# i-ching_2020-06-26_04-06-56.net
KiCad netlist of a schematic drawn in EasyEDA
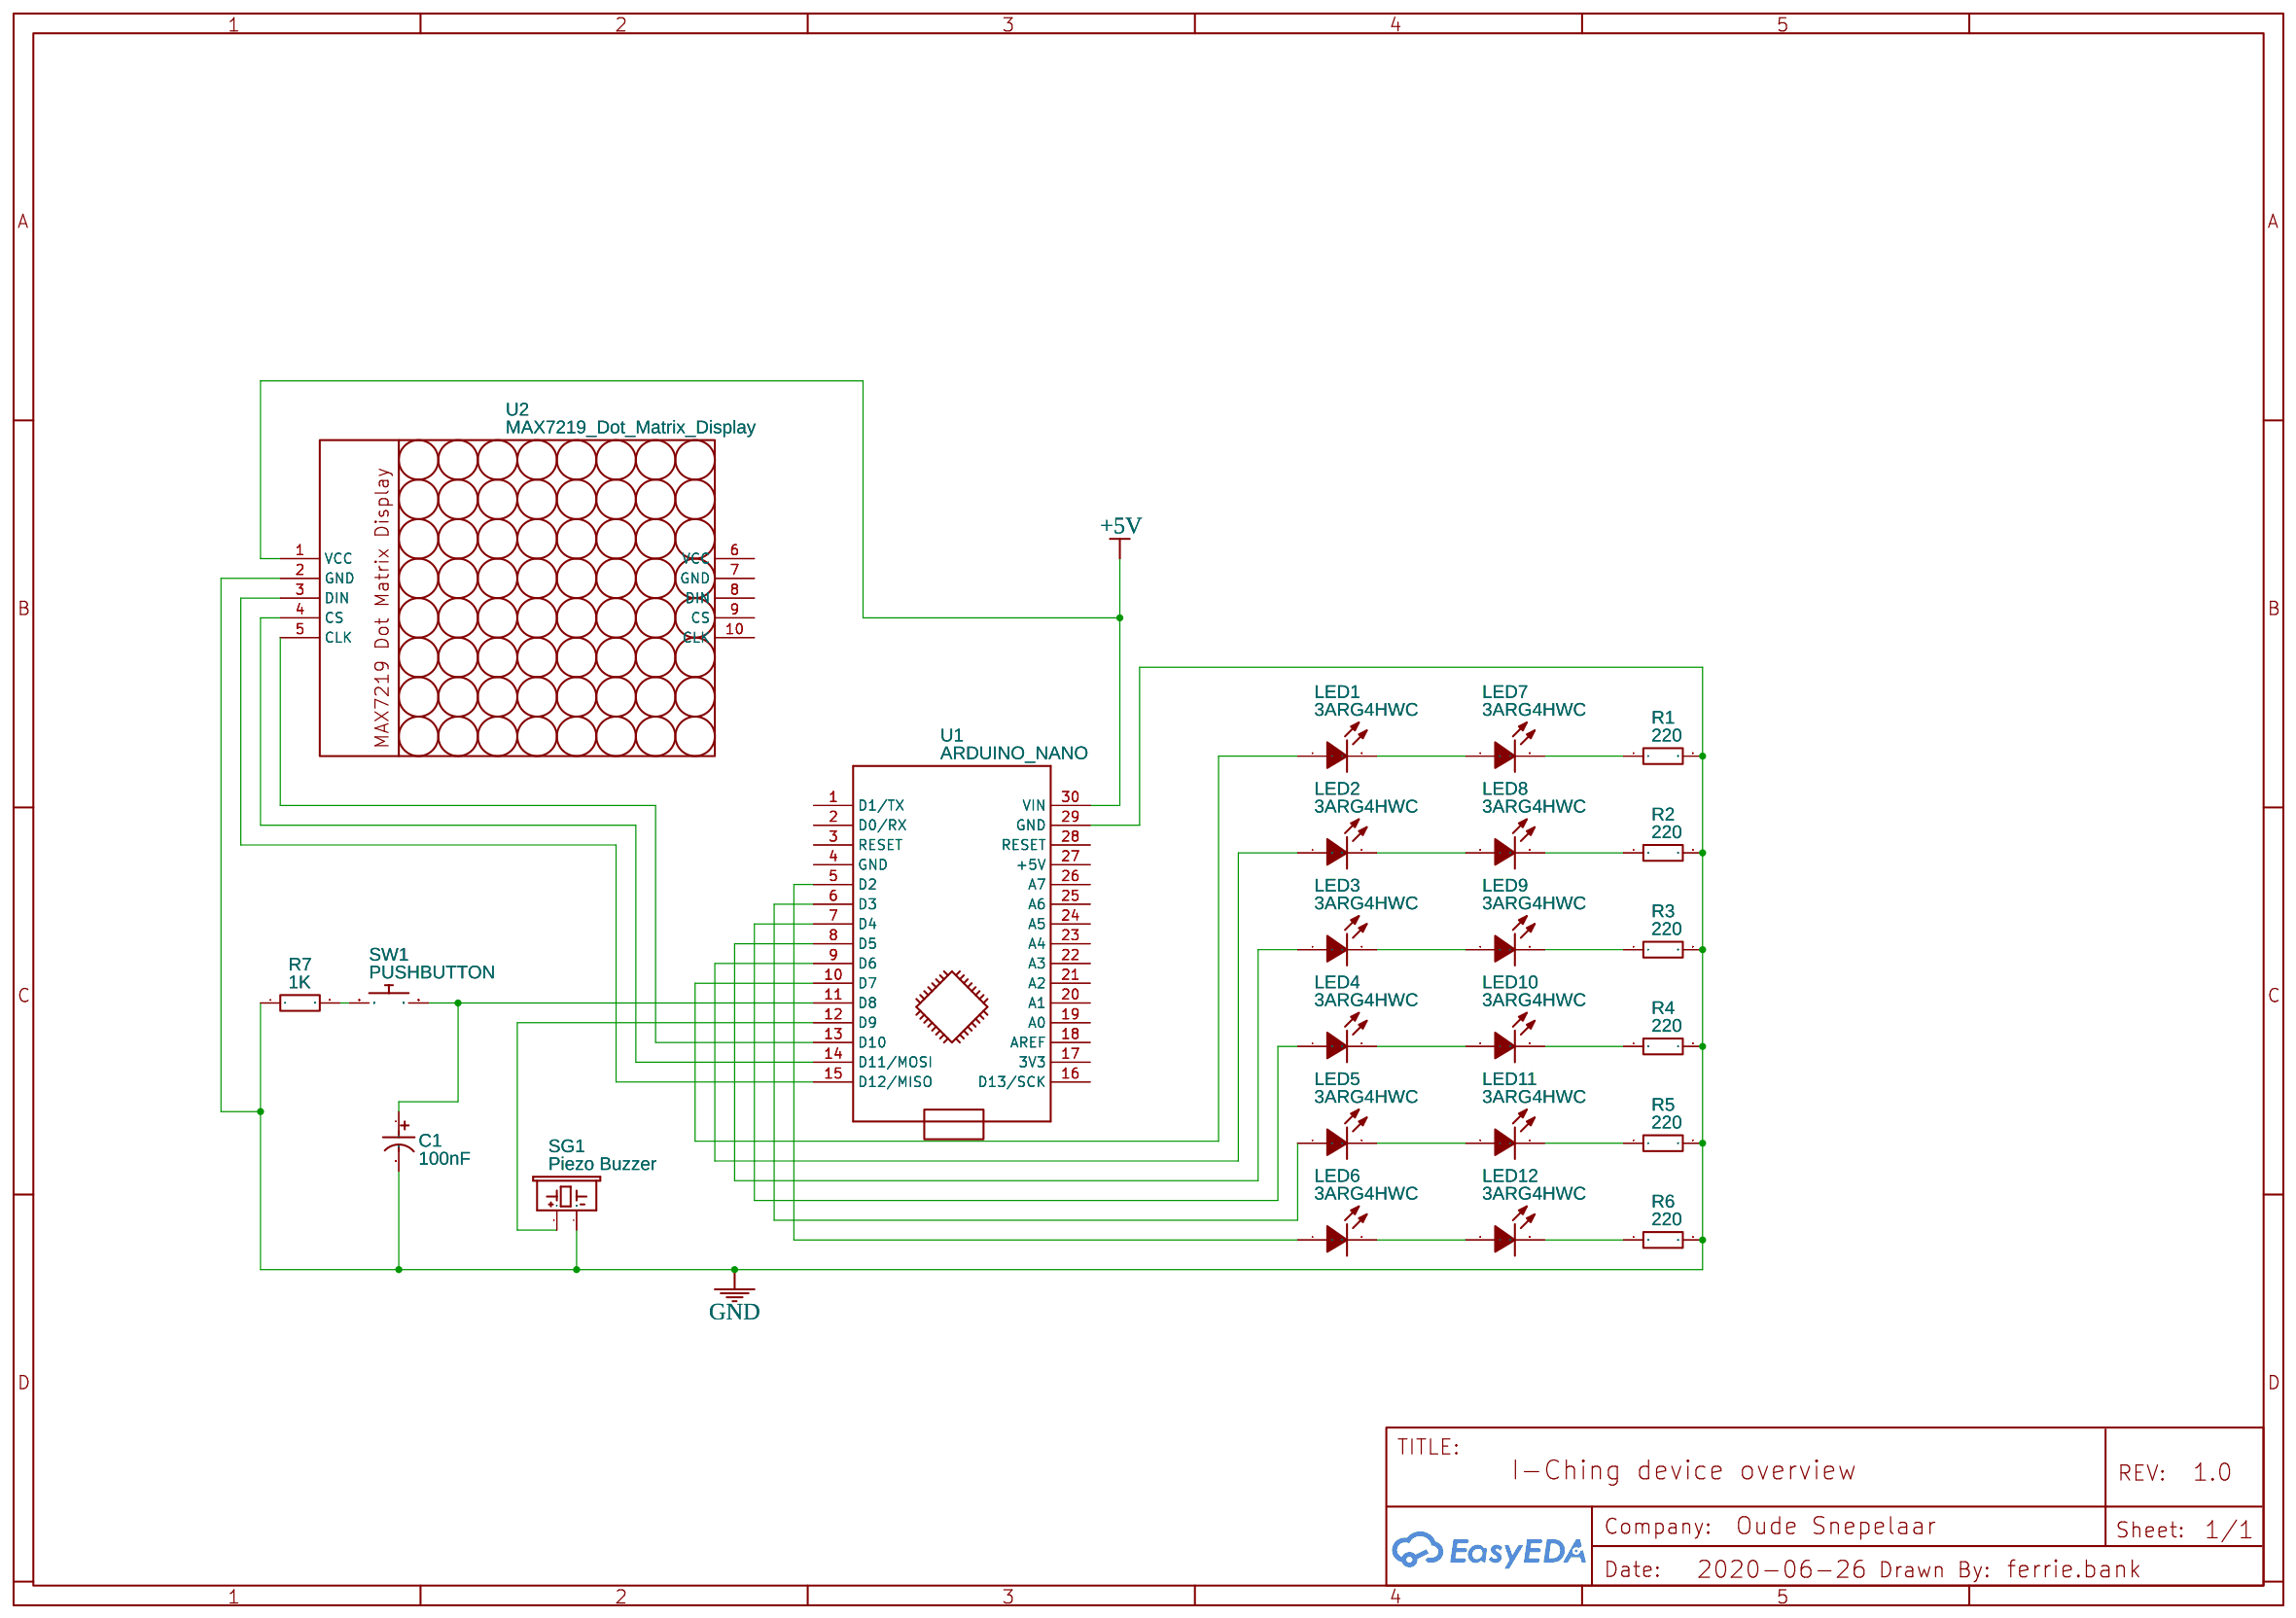
[diagram p0: I-Ching device overview]
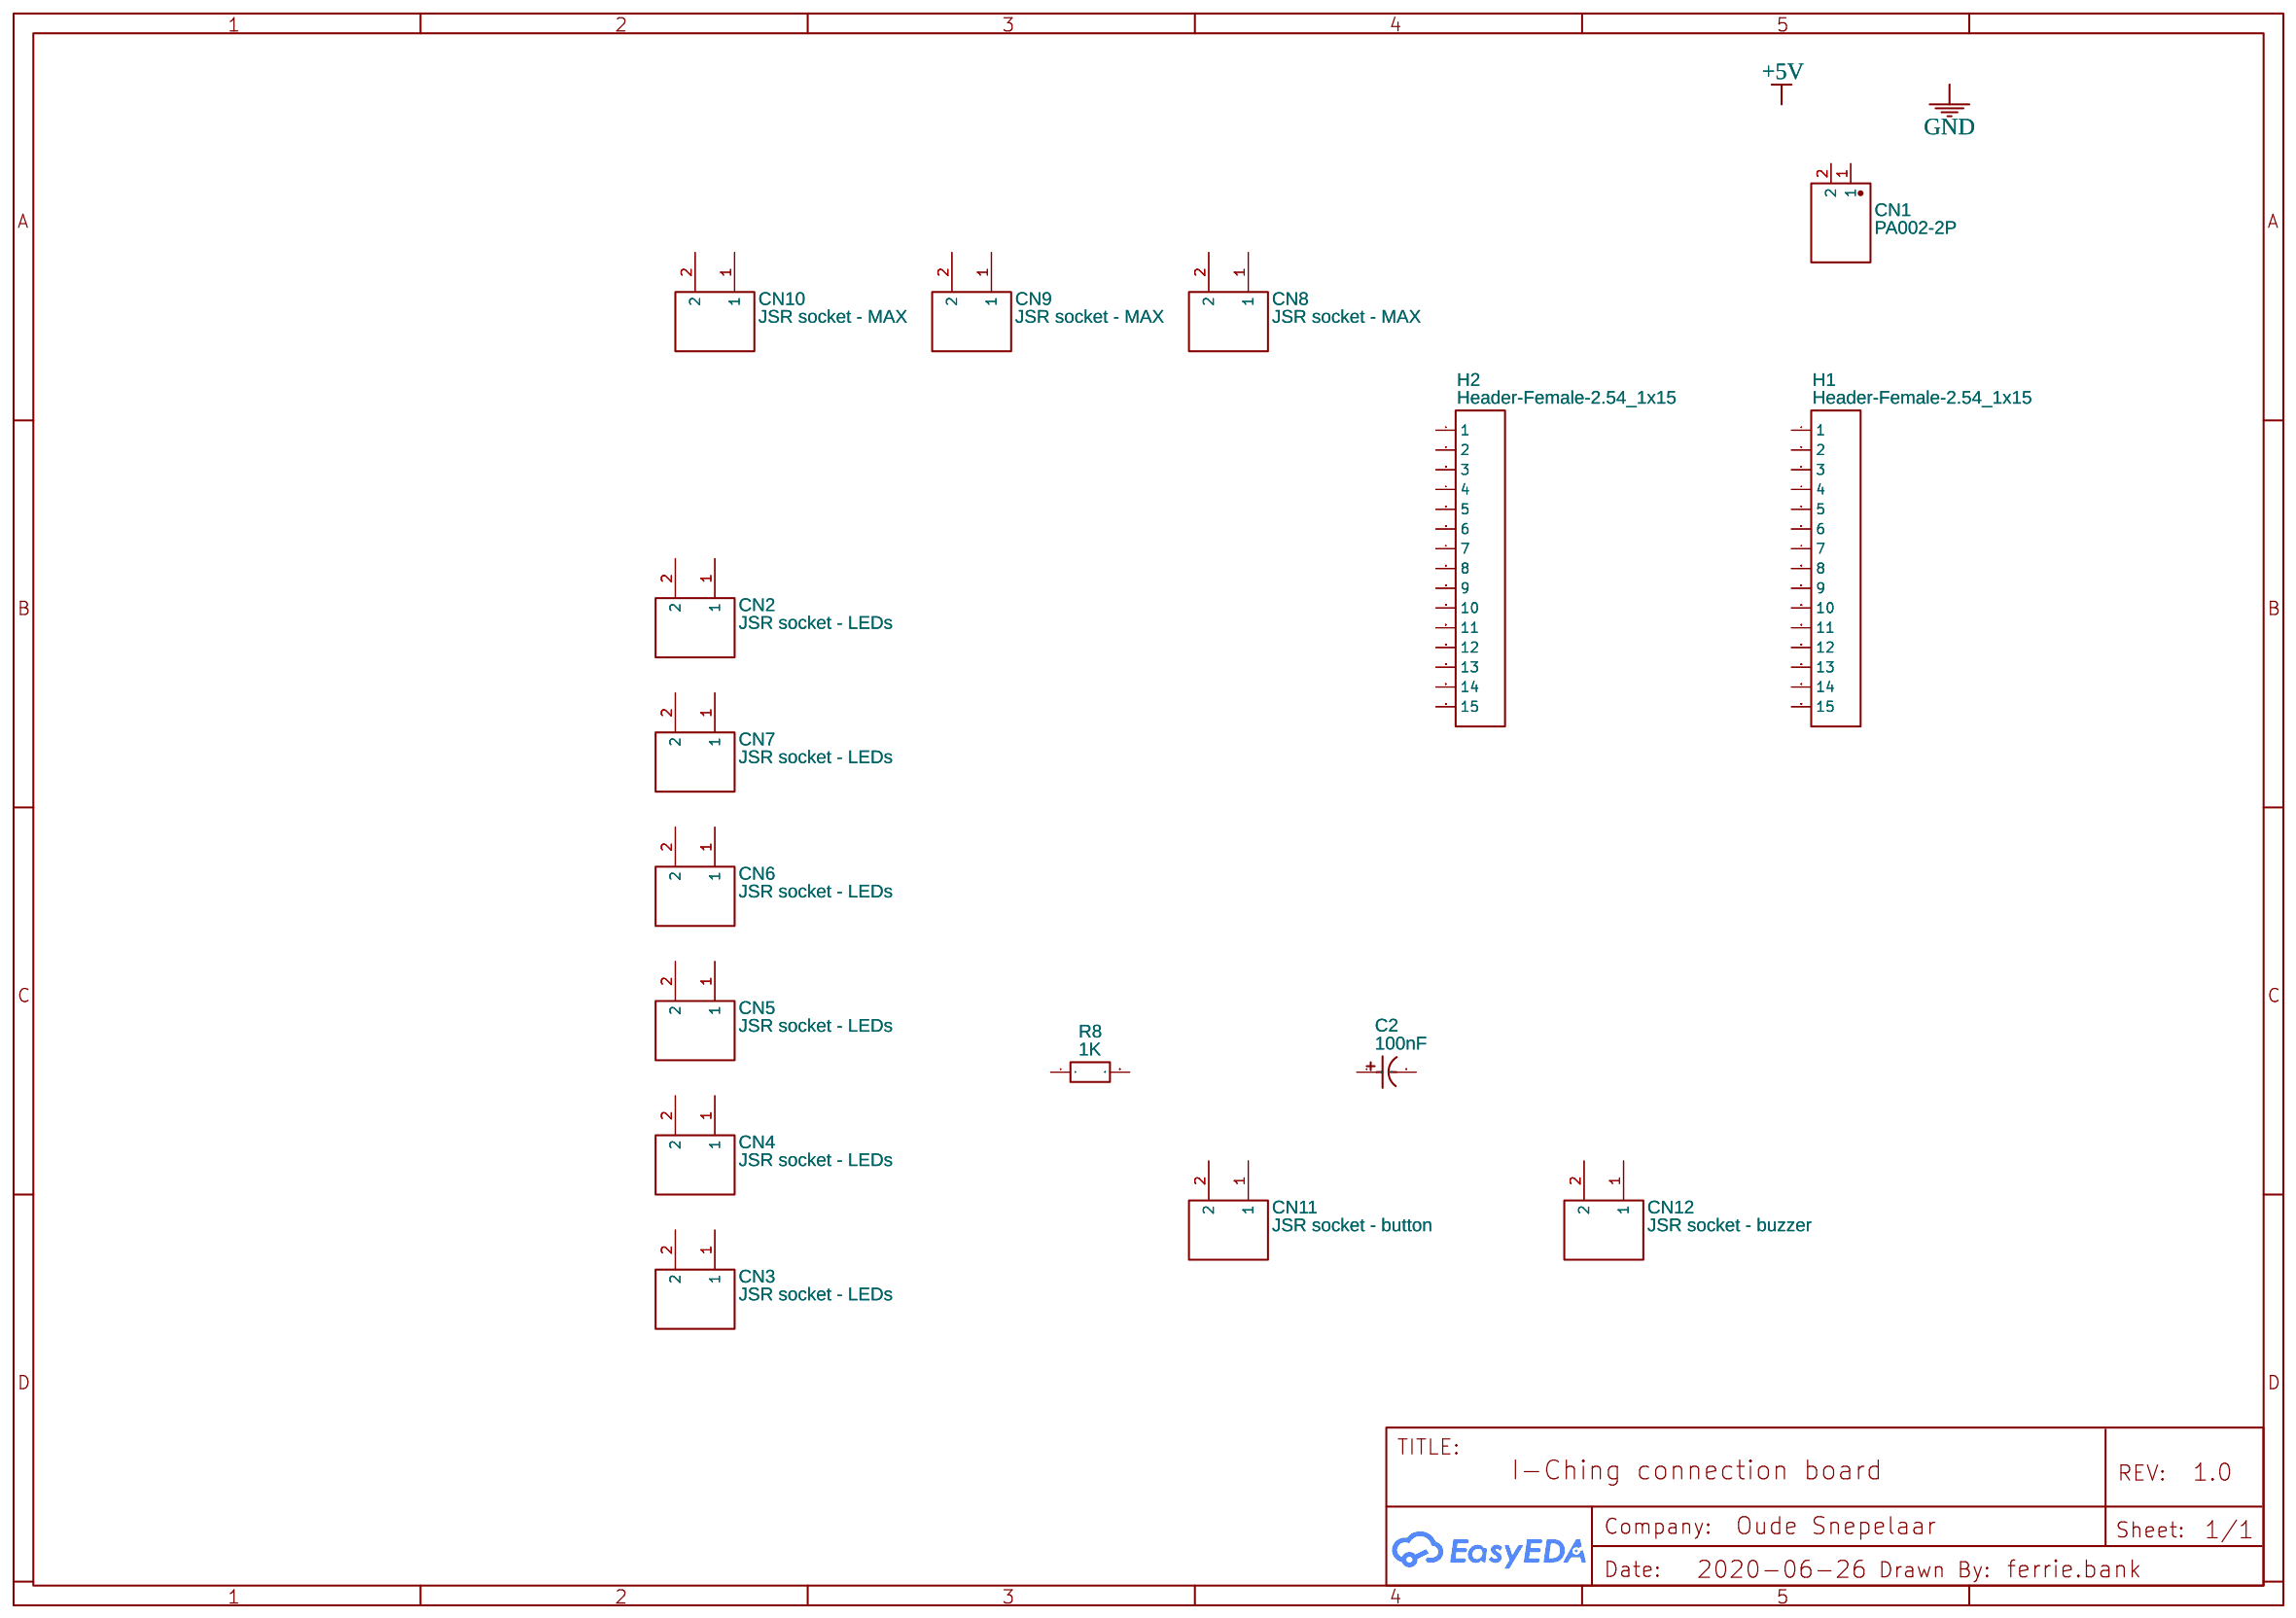
[diagram p1: I-Ching connection board]

(export (version "E")
  (design (tool "Eeschema 10.0.6"))
  (components
    (comp (ref "C1")
      (value "100nF")
      (fields (field (name "BOM_Manufacturer Part") "0.1UF 50V") (field (name "BOM_Supplier Part") "C28061"))
      (libsource (lib "") (part "0.1UF 50V"))
    )
    (comp (ref "LED1")
      (value "3ARG4HWC")
      (fields (field (name "BOM_Supplier Part") "C55640"))
      (libsource (lib "") (part "3ARG4HWC"))
    )
    (comp (ref "LED2")
      (value "3ARG4HWC")
      (fields (field (name "BOM_Supplier Part") "C55640"))
      (libsource (lib "") (part "3ARG4HWC"))
    )
    (comp (ref "LED3")
      (value "3ARG4HWC")
      (fields (field (name "BOM_Supplier Part") "C55640"))
      (libsource (lib "") (part "3ARG4HWC"))
    )
    (comp (ref "LED4")
      (value "3ARG4HWC")
      (fields (field (name "BOM_Supplier Part") "C55640"))
      (libsource (lib "") (part "3ARG4HWC"))
    )
    (comp (ref "LED5")
      (value "3ARG4HWC")
      (fields (field (name "BOM_Supplier Part") "C55640"))
      (libsource (lib "") (part "3ARG4HWC"))
    )
    (comp (ref "LED6")
      (value "3ARG4HWC")
      (fields (field (name "BOM_Supplier Part") "C55640"))
      (libsource (lib "") (part "3ARG4HWC"))
    )
    (comp (ref "LED7")
      (value "3ARG4HWC")
      (fields (field (name "BOM_Supplier Part") "C55640"))
      (libsource (lib "") (part "3ARG4HWC"))
    )
    (comp (ref "LED8")
      (value "3ARG4HWC")
      (fields (field (name "BOM_Supplier Part") "C55640"))
      (libsource (lib "") (part "3ARG4HWC"))
    )
    (comp (ref "LED9")
      (value "3ARG4HWC")
      (fields (field (name "BOM_Supplier Part") "C55640"))
      (libsource (lib "") (part "3ARG4HWC"))
    )
    (comp (ref "LED10")
      (value "3ARG4HWC")
      (fields (field (name "BOM_Supplier Part") "C55640"))
      (libsource (lib "") (part "3ARG4HWC"))
    )
    (comp (ref "LED11")
      (value "3ARG4HWC")
      (fields (field (name "BOM_Supplier Part") "C55640"))
      (libsource (lib "") (part "3ARG4HWC"))
    )
    (comp (ref "LED12")
      (value "3ARG4HWC")
      (fields (field (name "BOM_Supplier Part") "C55640"))
      (libsource (lib "") (part "3ARG4HWC"))
    )
    (comp (ref "R1")
      (value "220")
      (fields
        (field (name "BOM_Manufacturer Part") "MFR2WSJT-73-220R")
        (field (name "BOM_Supplier Part") "C176568")
      )
      (libsource (lib "") (part "MFR2WSJT-73-220R"))
    )
    (comp (ref "R2")
      (value "220")
      (fields
        (field (name "BOM_Manufacturer Part") "MFR2WSJT-73-220R")
        (field (name "BOM_Supplier Part") "C176568")
      )
      (libsource (lib "") (part "MFR2WSJT-73-220R"))
    )
    (comp (ref "R3")
      (value "220")
      (fields
        (field (name "BOM_Manufacturer Part") "MFR2WSJT-73-220R")
        (field (name "BOM_Supplier Part") "C176568")
      )
      (libsource (lib "") (part "MFR2WSJT-73-220R"))
    )
    (comp (ref "R4")
      (value "220")
      (fields
        (field (name "BOM_Manufacturer Part") "MFR2WSJT-73-220R")
        (field (name "BOM_Supplier Part") "C176568")
      )
      (libsource (lib "") (part "MFR2WSJT-73-220R"))
    )
    (comp (ref "R5")
      (value "220")
      (fields
        (field (name "BOM_Manufacturer Part") "MFR2WSJT-73-220R")
        (field (name "BOM_Supplier Part") "C176568")
      )
      (libsource (lib "") (part "MFR2WSJT-73-220R"))
    )
    (comp (ref "R6")
      (value "220")
      (fields
        (field (name "BOM_Manufacturer Part") "MFR2WSJT-73-220R")
        (field (name "BOM_Supplier Part") "C176568")
      )
      (libsource (lib "") (part "MFR2WSJT-73-220R"))
    )
    (comp (ref "R7")
      (value "1K")
      (fields
        (field (name "BOM_Manufacturer Part") "MFR02SF1001A10")
        (field (name "BOM_Supplier Part") "C58742")
      )
      (libsource (lib "") (part "MFR02SF1001A10"))
    )
    (comp (ref "SG1") (value "Piezo Buzzer") (libsource (lib "") (part "Piezo Buzzer")))
    (comp (ref "SW1") (value "PUSHBUTTON") (libsource (lib "") (part "SWITCH_PUSHBUTTONCK_KSS")))
    (comp (ref "U1") (value "ARDUINO_NANO") (libsource (lib "") (part "ARDUINO_NANO")))
    (comp (ref "U2")
      (value "MAX7219_Dot_Matrix_Display")
      (libsource (lib "") (part "MAX7219_Dot_Matrix_Display"))
    )
    (comp (ref "C2")
      (value "100nF")
      (fields (field (name "BOM_Manufacturer Part") "0.1UF 50V") (field (name "BOM_Supplier Part") "C28061"))
      (libsource (lib "") (part "0.1UF 50V"))
    )
    (comp (ref "CN1")
      (value "PA002-2P")
      (fields (field (name "BOM_Supplier Part") "C163148"))
      (libsource (lib "") (part "PA002-2P"))
    )
    (comp (ref "CN2")
      (value "JSR socket - LEDs")
      (fields
        (field (name "BOM_Manufacturer Part") "socket.blue5566-2Aneedle")
        (field (name "BOM_Supplier Part") "C62133")
      )
      (libsource (lib "") (part "socket.blue5566-2Aneedle"))
    )
    (comp (ref "CN3")
      (value "JSR socket - LEDs")
      (fields
        (field (name "BOM_Manufacturer Part") "socket.blue5566-2Aneedle")
        (field (name "BOM_Supplier Part") "C62133")
      )
      (libsource (lib "") (part "socket.blue5566-2Aneedle"))
    )
    (comp (ref "CN4")
      (value "JSR socket - LEDs")
      (fields
        (field (name "BOM_Manufacturer Part") "socket.blue5566-2Aneedle")
        (field (name "BOM_Supplier Part") "C62133")
      )
      (libsource (lib "") (part "socket.blue5566-2Aneedle"))
    )
    (comp (ref "CN5")
      (value "JSR socket - LEDs")
      (fields
        (field (name "BOM_Manufacturer Part") "socket.blue5566-2Aneedle")
        (field (name "BOM_Supplier Part") "C62133")
      )
      (libsource (lib "") (part "socket.blue5566-2Aneedle"))
    )
    (comp (ref "CN6")
      (value "JSR socket - LEDs")
      (fields
        (field (name "BOM_Manufacturer Part") "socket.blue5566-2Aneedle")
        (field (name "BOM_Supplier Part") "C62133")
      )
      (libsource (lib "") (part "socket.blue5566-2Aneedle"))
    )
    (comp (ref "CN7")
      (value "JSR socket - LEDs")
      (fields
        (field (name "BOM_Manufacturer Part") "socket.blue5566-2Aneedle")
        (field (name "BOM_Supplier Part") "C62133")
      )
      (libsource (lib "") (part "socket.blue5566-2Aneedle"))
    )
    (comp (ref "CN8")
      (value "JSR socket - MAX")
      (fields
        (field (name "BOM_Manufacturer Part") "socket.blue5566-2Aneedle")
        (field (name "BOM_Supplier Part") "C62133")
      )
      (libsource (lib "") (part "socket.blue5566-2Aneedle"))
    )
    (comp (ref "CN9")
      (value "JSR socket - MAX")
      (fields
        (field (name "BOM_Manufacturer Part") "socket.blue5566-2Aneedle")
        (field (name "BOM_Supplier Part") "C62133")
      )
      (libsource (lib "") (part "socket.blue5566-2Aneedle"))
    )
    (comp (ref "CN10")
      (value "JSR socket - MAX")
      (fields
        (field (name "BOM_Manufacturer Part") "socket.blue5566-2Aneedle")
        (field (name "BOM_Supplier Part") "C62133")
      )
      (libsource (lib "") (part "socket.blue5566-2Aneedle"))
    )
    (comp (ref "CN11")
      (value "JSR socket - button")
      (fields
        (field (name "BOM_Manufacturer Part") "socket.blue5566-2Aneedle")
        (field (name "BOM_Supplier Part") "C62133")
      )
      (libsource (lib "") (part "socket.blue5566-2Aneedle"))
    )
    (comp (ref "CN12")
      (value "JSR socket - buzzer")
      (fields
        (field (name "BOM_Manufacturer Part") "socket.blue5566-2Aneedle")
        (field (name "BOM_Supplier Part") "C62133")
      )
      (libsource (lib "") (part "socket.blue5566-2Aneedle"))
    )
    (comp (ref "H1")
      (value "Header-Female-2.54_1x15")
      (fields
        (field (name "BOM_Manufacturer Part") "220S-1*15P H=8.5MM Ytype Gold-plated")
        (field (name "BOM_Supplier Part") "C124408")
      )
      (libsource (lib "") (part "Header-Female-2.54_1x15"))
    )
    (comp (ref "H2")
      (value "Header-Female-2.54_1x15")
      (fields
        (field (name "BOM_Manufacturer Part") "220S-1*15P H=8.5MM Ytype Gold-plated")
        (field (name "BOM_Supplier Part") "C124408")
      )
      (libsource (lib "") (part "Header-Female-2.54_1x15"))
    )
    (comp (ref "R8")
      (value "1K")
      (fields
        (field (name "BOM_Manufacturer Part") "RN 2WS 1K F T/B A1")
        (field (name "BOM_Supplier Part") "C433624")
      )
      (libsource (lib "") (part "RN 2WS 1K F T/B A1_C433624"))
    )
  )
  (nets
    (net (code "1") (name "+5V") (class "Default")
      (node (ref "U1") (pin "30") (pinfunction "VIN_30") (pintype "unspecified"))
      (node (ref "U2") (pin "1") (pinfunction "VCC_1") (pintype "unspecified"))
    )
    (net (code "2") (name "GND") (class "Default")
      (node (ref "C1") (pin "2") (pinfunction "2_2") (pintype "input"))
      (node (ref "R1") (pin "2") (pinfunction "2_2") (pintype "input"))
      (node (ref "R2") (pin "2") (pinfunction "2_2") (pintype "input"))
      (node (ref "R3") (pin "2") (pinfunction "2_2") (pintype "input"))
      (node (ref "R4") (pin "2") (pinfunction "2_2") (pintype "input"))
      (node (ref "R5") (pin "2") (pinfunction "2_2") (pintype "input"))
      (node (ref "R6") (pin "2") (pinfunction "2_2") (pintype "input"))
      (node (ref "R7") (pin "1") (pinfunction "1_1") (pintype "input"))
      (node (ref "SG1") (pin "-") (pinfunction "2_-") (pintype "unspecified"))
      (node (ref "U1") (pin "29") (pinfunction "GND_29") (pintype "unspecified"))
      (node (ref "U2") (pin "2") (pinfunction "GND_2") (pintype "unspecified"))
    )
    (net (code "3") (name "Net-(LED1-A)") (class "Default")
      (node (ref "LED1") (pin "1") (pinfunction "A_1") (pintype "unspecified"))
      (node (ref "U1") (pin "10") (pinfunction "D7_10") (pintype "unspecified"))
    )
    (net (code "4") (name "Net-(LED1-K)") (class "Default")
      (node (ref "LED1") (pin "2") (pinfunction "K_2") (pintype "unspecified"))
      (node (ref "LED7") (pin "1") (pinfunction "A_1") (pintype "unspecified"))
    )
    (net (code "5") (name "Net-(LED2-A)") (class "Default")
      (node (ref "LED2") (pin "1") (pinfunction "A_1") (pintype "unspecified"))
      (node (ref "U1") (pin "9") (pinfunction "D6_9") (pintype "unspecified"))
    )
    (net (code "6") (name "Net-(LED2-K)") (class "Default")
      (node (ref "LED2") (pin "2") (pinfunction "K_2") (pintype "unspecified"))
      (node (ref "LED8") (pin "1") (pinfunction "A_1") (pintype "unspecified"))
    )
    (net (code "7") (name "Net-(LED3-A)") (class "Default")
      (node (ref "LED3") (pin "1") (pinfunction "A_1") (pintype "unspecified"))
      (node (ref "U1") (pin "8") (pinfunction "D5_8") (pintype "unspecified"))
    )
    (net (code "8") (name "Net-(LED3-K)") (class "Default")
      (node (ref "LED3") (pin "2") (pinfunction "K_2") (pintype "unspecified"))
      (node (ref "LED9") (pin "1") (pinfunction "A_1") (pintype "unspecified"))
    )
    (net (code "9") (name "Net-(LED4-A)") (class "Default")
      (node (ref "LED4") (pin "1") (pinfunction "A_1") (pintype "unspecified"))
      (node (ref "U1") (pin "7") (pinfunction "D4_7") (pintype "unspecified"))
    )
    (net (code "10") (name "Net-(LED5-A)") (class "Default")
      (node (ref "LED5") (pin "1") (pinfunction "A_1") (pintype "unspecified"))
      (node (ref "U1") (pin "6") (pinfunction "D3_6") (pintype "unspecified"))
    )
    (net (code "11") (name "Net-(LED6-A)") (class "Default")
      (node (ref "LED6") (pin "1") (pinfunction "A_1") (pintype "unspecified"))
      (node (ref "U1") (pin "5") (pinfunction "D2_5") (pintype "unspecified"))
    )
    (net (code "12") (name "Net-(LED7-K)") (class "Default")
      (node (ref "LED7") (pin "2") (pinfunction "K_2") (pintype "unspecified"))
      (node (ref "R1") (pin "1") (pinfunction "1_1") (pintype "input"))
    )
    (net (code "13") (name "Net-(LED8-K)") (class "Default")
      (node (ref "LED8") (pin "2") (pinfunction "K_2") (pintype "unspecified"))
      (node (ref "R2") (pin "1") (pinfunction "1_1") (pintype "input"))
    )
    (net (code "14") (name "Net-(LED9-K)") (class "Default")
      (node (ref "LED9") (pin "2") (pinfunction "K_2") (pintype "unspecified"))
      (node (ref "R3") (pin "1") (pinfunction "1_1") (pintype "input"))
    )
    (net (code "15") (name "Net-(LED10-A)") (class "Default")
      (node (ref "LED10") (pin "1") (pinfunction "A_1") (pintype "unspecified"))
      (node (ref "LED4") (pin "2") (pinfunction "K_2") (pintype "unspecified"))
    )
    (net (code "16") (name "Net-(LED10-K)") (class "Default")
      (node (ref "LED10") (pin "2") (pinfunction "K_2") (pintype "unspecified"))
      (node (ref "R4") (pin "1") (pinfunction "1_1") (pintype "input"))
    )
    (net (code "17") (name "Net-(LED11-A)") (class "Default")
      (node (ref "LED11") (pin "1") (pinfunction "A_1") (pintype "unspecified"))
      (node (ref "LED5") (pin "2") (pinfunction "K_2") (pintype "unspecified"))
    )
    (net (code "18") (name "Net-(LED11-K)") (class "Default")
      (node (ref "LED11") (pin "2") (pinfunction "K_2") (pintype "unspecified"))
      (node (ref "R5") (pin "1") (pinfunction "1_1") (pintype "input"))
    )
    (net (code "19") (name "Net-(LED12-A)") (class "Default")
      (node (ref "LED12") (pin "1") (pinfunction "A_1") (pintype "unspecified"))
      (node (ref "LED6") (pin "2") (pinfunction "K_2") (pintype "unspecified"))
    )
    (net (code "20") (name "Net-(LED12-K)") (class "Default")
      (node (ref "LED12") (pin "2") (pinfunction "K_2") (pintype "unspecified"))
      (node (ref "R6") (pin "1") (pinfunction "1_1") (pintype "input"))
    )
    (net (code "21") (name "Net-(R7-Pad2)") (class "Default")
      (node (ref "R7") (pin "2") (pinfunction "2_2") (pintype "input"))
      (node (ref "SW1") (pin "P$1") (pinfunction "P$1_P$1") (pintype "unspecified"))
    )
    (net (code "22") (name "Net-(SG1-1)") (class "Default")
      (node (ref "SG1") (pin "+") (pinfunction "1_+") (pintype "unspecified"))
      (node (ref "U1") (pin "12") (pinfunction "D9_12") (pintype "unspecified"))
    )
    (net (code "23") (name "Net-(U1-D8)") (class "Default")
      (node (ref "C1") (pin "1") (pinfunction "1_1") (pintype "input"))
      (node (ref "SW1") (pin "P$2") (pinfunction "P$2_P$2") (pintype "unspecified"))
      (node (ref "U1") (pin "11") (pinfunction "D8_11") (pintype "unspecified"))
    )
    (net (code "24") (name "Net-(U1-D10)") (class "Default")
      (node (ref "U1") (pin "13") (pinfunction "D10_13") (pintype "unspecified"))
      (node (ref "U2") (pin "5") (pinfunction "CLK_5") (pintype "unspecified"))
    )
    (net (code "25") (name "Net-(U1-D11{slash}MOSI)") (class "Default")
      (node (ref "U1") (pin "14") (pinfunction "D11/MOSI_14") (pintype "unspecified"))
      (node (ref "U2") (pin "4") (pinfunction "CS_4") (pintype "unspecified"))
    )
    (net (code "26") (name "Net-(U1-D12{slash}MISO)") (class "Default")
      (node (ref "U1") (pin "15") (pinfunction "D12/MISO_15") (pintype "unspecified"))
      (node (ref "U2") (pin "3") (pinfunction "DIN_3") (pintype "unspecified"))
    )
    (net (code "27") (name "unconnected-(C2-Pad1)") (class "Default")
      (node (ref "C2") (pin "1") (pinfunction "1_1") (pintype "input"))
    )
    (net (code "28") (name "unconnected-(C2-Pad2)") (class "Default")
      (node (ref "C2") (pin "2") (pinfunction "2_2") (pintype "input"))
    )
    (net (code "29") (name "unconnected-(CN1-Pad1)") (class "Default")
      (node (ref "CN1") (pin "1") (pinfunction "1_1") (pintype "unspecified"))
    )
    (net (code "30") (name "unconnected-(CN1-Pad2)") (class "Default")
      (node (ref "CN1") (pin "2") (pinfunction "2_2") (pintype "unspecified"))
    )
    (net (code "31") (name "unconnected-(CN2-Pad1)") (class "Default")
      (node (ref "CN2") (pin "1") (pinfunction "1_1") (pintype "unspecified"))
    )
    (net (code "32") (name "unconnected-(CN2-Pad2)") (class "Default")
      (node (ref "CN2") (pin "2") (pinfunction "2_2") (pintype "unspecified"))
    )
    (net (code "33") (name "unconnected-(CN3-Pad1)") (class "Default")
      (node (ref "CN3") (pin "1") (pinfunction "1_1") (pintype "unspecified"))
    )
    (net (code "34") (name "unconnected-(CN3-Pad2)") (class "Default")
      (node (ref "CN3") (pin "2") (pinfunction "2_2") (pintype "unspecified"))
    )
    (net (code "35") (name "unconnected-(CN4-Pad1)") (class "Default")
      (node (ref "CN4") (pin "1") (pinfunction "1_1") (pintype "unspecified"))
    )
    (net (code "36") (name "unconnected-(CN4-Pad2)") (class "Default")
      (node (ref "CN4") (pin "2") (pinfunction "2_2") (pintype "unspecified"))
    )
    (net (code "37") (name "unconnected-(CN5-Pad1)") (class "Default")
      (node (ref "CN5") (pin "1") (pinfunction "1_1") (pintype "unspecified"))
    )
    (net (code "38") (name "unconnected-(CN5-Pad2)") (class "Default")
      (node (ref "CN5") (pin "2") (pinfunction "2_2") (pintype "unspecified"))
    )
    (net (code "39") (name "unconnected-(CN6-Pad1)") (class "Default")
      (node (ref "CN6") (pin "1") (pinfunction "1_1") (pintype "unspecified"))
    )
    (net (code "40") (name "unconnected-(CN6-Pad2)") (class "Default")
      (node (ref "CN6") (pin "2") (pinfunction "2_2") (pintype "unspecified"))
    )
    (net (code "41") (name "unconnected-(CN7-Pad1)") (class "Default")
      (node (ref "CN7") (pin "1") (pinfunction "1_1") (pintype "unspecified"))
    )
    (net (code "42") (name "unconnected-(CN7-Pad2)") (class "Default")
      (node (ref "CN7") (pin "2") (pinfunction "2_2") (pintype "unspecified"))
    )
    (net (code "43") (name "unconnected-(CN8-Pad1)") (class "Default")
      (node (ref "CN8") (pin "1") (pinfunction "1_1") (pintype "unspecified"))
    )
    (net (code "44") (name "unconnected-(CN8-Pad2)") (class "Default")
      (node (ref "CN8") (pin "2") (pinfunction "2_2") (pintype "unspecified"))
    )
    (net (code "45") (name "unconnected-(CN9-Pad1)") (class "Default")
      (node (ref "CN9") (pin "1") (pinfunction "1_1") (pintype "unspecified"))
    )
    (net (code "46") (name "unconnected-(CN9-Pad2)") (class "Default")
      (node (ref "CN9") (pin "2") (pinfunction "2_2") (pintype "unspecified"))
    )
    (net (code "47") (name "unconnected-(CN10-Pad1)") (class "Default")
      (node (ref "CN10") (pin "1") (pinfunction "1_1") (pintype "unspecified"))
    )
    (net (code "48") (name "unconnected-(CN10-Pad2)") (class "Default")
      (node (ref "CN10") (pin "2") (pinfunction "2_2") (pintype "unspecified"))
    )
    (net (code "49") (name "unconnected-(CN11-Pad1)") (class "Default")
      (node (ref "CN11") (pin "1") (pinfunction "1_1") (pintype "unspecified"))
    )
    (net (code "50") (name "unconnected-(CN11-Pad2)") (class "Default")
      (node (ref "CN11") (pin "2") (pinfunction "2_2") (pintype "unspecified"))
    )
    (net (code "51") (name "unconnected-(CN12-Pad1)") (class "Default")
      (node (ref "CN12") (pin "1") (pinfunction "1_1") (pintype "unspecified"))
    )
    (net (code "52") (name "unconnected-(CN12-Pad2)") (class "Default")
      (node (ref "CN12") (pin "2") (pinfunction "2_2") (pintype "unspecified"))
    )
    (net (code "53") (name "unconnected-(H1-Pad1)") (class "Default")
      (node (ref "H1") (pin "1") (pinfunction "1_1") (pintype "unspecified"))
    )
    (net (code "54") (name "unconnected-(H1-Pad2)") (class "Default")
      (node (ref "H1") (pin "2") (pinfunction "2_2") (pintype "unspecified"))
    )
    (net (code "55") (name "unconnected-(H1-Pad3)") (class "Default")
      (node (ref "H1") (pin "3") (pinfunction "3_3") (pintype "unspecified"))
    )
    (net (code "56") (name "unconnected-(H1-Pad4)") (class "Default")
      (node (ref "H1") (pin "4") (pinfunction "4_4") (pintype "unspecified"))
    )
    (net (code "57") (name "unconnected-(H1-Pad5)") (class "Default")
      (node (ref "H1") (pin "5") (pinfunction "5_5") (pintype "unspecified"))
    )
    (net (code "58") (name "unconnected-(H1-Pad6)") (class "Default")
      (node (ref "H1") (pin "6") (pinfunction "6_6") (pintype "unspecified"))
    )
    (net (code "59") (name "unconnected-(H1-Pad7)") (class "Default")
      (node (ref "H1") (pin "7") (pinfunction "7_7") (pintype "unspecified"))
    )
    (net (code "60") (name "unconnected-(H1-Pad8)") (class "Default")
      (node (ref "H1") (pin "8") (pinfunction "8_8") (pintype "unspecified"))
    )
    (net (code "61") (name "unconnected-(H1-Pad9)") (class "Default")
      (node (ref "H1") (pin "9") (pinfunction "9_9") (pintype "unspecified"))
    )
    (net (code "62") (name "unconnected-(H1-Pad10)") (class "Default")
      (node (ref "H1") (pin "10") (pinfunction "10_10") (pintype "unspecified"))
    )
    (net (code "63") (name "unconnected-(H1-Pad11)") (class "Default")
      (node (ref "H1") (pin "11") (pinfunction "11_11") (pintype "unspecified"))
    )
    (net (code "64") (name "unconnected-(H1-Pad12)") (class "Default")
      (node (ref "H1") (pin "12") (pinfunction "12_12") (pintype "unspecified"))
    )
    (net (code "65") (name "unconnected-(H1-Pad13)") (class "Default")
      (node (ref "H1") (pin "13") (pinfunction "13_13") (pintype "unspecified"))
    )
    (net (code "66") (name "unconnected-(H1-Pad14)") (class "Default")
      (node (ref "H1") (pin "14") (pinfunction "14_14") (pintype "unspecified"))
    )
    (net (code "67") (name "unconnected-(H1-Pad15)") (class "Default")
      (node (ref "H1") (pin "15") (pinfunction "15_15") (pintype "unspecified"))
    )
    (net (code "68") (name "unconnected-(H2-Pad1)") (class "Default")
      (node (ref "H2") (pin "1") (pinfunction "1_1") (pintype "unspecified"))
    )
    (net (code "69") (name "unconnected-(H2-Pad2)") (class "Default")
      (node (ref "H2") (pin "2") (pinfunction "2_2") (pintype "unspecified"))
    )
    (net (code "70") (name "unconnected-(H2-Pad3)") (class "Default")
      (node (ref "H2") (pin "3") (pinfunction "3_3") (pintype "unspecified"))
    )
    (net (code "71") (name "unconnected-(H2-Pad4)") (class "Default")
      (node (ref "H2") (pin "4") (pinfunction "4_4") (pintype "unspecified"))
    )
    (net (code "72") (name "unconnected-(H2-Pad5)") (class "Default")
      (node (ref "H2") (pin "5") (pinfunction "5_5") (pintype "unspecified"))
    )
    (net (code "73") (name "unconnected-(H2-Pad6)") (class "Default")
      (node (ref "H2") (pin "6") (pinfunction "6_6") (pintype "unspecified"))
    )
    (net (code "74") (name "unconnected-(H2-Pad7)") (class "Default")
      (node (ref "H2") (pin "7") (pinfunction "7_7") (pintype "unspecified"))
    )
    (net (code "75") (name "unconnected-(H2-Pad8)") (class "Default")
      (node (ref "H2") (pin "8") (pinfunction "8_8") (pintype "unspecified"))
    )
    (net (code "76") (name "unconnected-(H2-Pad9)") (class "Default")
      (node (ref "H2") (pin "9") (pinfunction "9_9") (pintype "unspecified"))
    )
    (net (code "77") (name "unconnected-(H2-Pad10)") (class "Default")
      (node (ref "H2") (pin "10") (pinfunction "10_10") (pintype "unspecified"))
    )
    (net (code "78") (name "unconnected-(H2-Pad11)") (class "Default")
      (node (ref "H2") (pin "11") (pinfunction "11_11") (pintype "unspecified"))
    )
    (net (code "79") (name "unconnected-(H2-Pad12)") (class "Default")
      (node (ref "H2") (pin "12") (pinfunction "12_12") (pintype "unspecified"))
    )
    (net (code "80") (name "unconnected-(H2-Pad13)") (class "Default")
      (node (ref "H2") (pin "13") (pinfunction "13_13") (pintype "unspecified"))
    )
    (net (code "81") (name "unconnected-(H2-Pad14)") (class "Default")
      (node (ref "H2") (pin "14") (pinfunction "14_14") (pintype "unspecified"))
    )
    (net (code "82") (name "unconnected-(H2-Pad15)") (class "Default")
      (node (ref "H2") (pin "15") (pinfunction "15_15") (pintype "unspecified"))
    )
    (net (code "83") (name "unconnected-(R8-Pad1)") (class "Default")
      (node (ref "R8") (pin "1") (pinfunction "1_1") (pintype "unspecified"))
    )
    (net (code "84") (name "unconnected-(R8-Pad2)") (class "Default")
      (node (ref "R8") (pin "2") (pinfunction "2_2") (pintype "unspecified"))
    )
    (net (code "85") (name "unconnected-(U1-+5V-Pad27)") (class "Default")
      (node (ref "U1") (pin "27") (pinfunction "+5V_27") (pintype "unspecified"))
    )
    (net (code "86") (name "unconnected-(U1-3V3-Pad17)") (class "Default")
      (node (ref "U1") (pin "17") (pinfunction "3V3_17") (pintype "unspecified"))
    )
    (net (code "87") (name "unconnected-(U1-A0-Pad19)") (class "Default")
      (node (ref "U1") (pin "19") (pinfunction "A0_19") (pintype "unspecified"))
    )
    (net (code "88") (name "unconnected-(U1-A1-Pad20)") (class "Default")
      (node (ref "U1") (pin "20") (pinfunction "A1_20") (pintype "unspecified"))
    )
    (net (code "89") (name "unconnected-(U1-A2-Pad21)") (class "Default")
      (node (ref "U1") (pin "21") (pinfunction "A2_21") (pintype "unspecified"))
    )
    (net (code "90") (name "unconnected-(U1-A3-Pad22)") (class "Default")
      (node (ref "U1") (pin "22") (pinfunction "A3_22") (pintype "unspecified"))
    )
    (net (code "91") (name "unconnected-(U1-A4-Pad23)") (class "Default")
      (node (ref "U1") (pin "23") (pinfunction "A4_23") (pintype "unspecified"))
    )
    (net (code "92") (name "unconnected-(U1-A5-Pad24)") (class "Default")
      (node (ref "U1") (pin "24") (pinfunction "A5_24") (pintype "unspecified"))
    )
    (net (code "93") (name "unconnected-(U1-A6-Pad25)") (class "Default")
      (node (ref "U1") (pin "25") (pinfunction "A6_25") (pintype "unspecified"))
    )
    (net (code "94") (name "unconnected-(U1-A7-Pad26)") (class "Default")
      (node (ref "U1") (pin "26") (pinfunction "A7_26") (pintype "unspecified"))
    )
    (net (code "95") (name "unconnected-(U1-AREF-Pad18)") (class "Default")
      (node (ref "U1") (pin "18") (pinfunction "AREF_18") (pintype "unspecified"))
    )
    (net (code "96") (name "unconnected-(U1-D0{slash}RX-Pad2)") (class "Default")
      (node (ref "U1") (pin "2") (pinfunction "D0/RX_2") (pintype "unspecified"))
    )
    (net (code "97") (name "unconnected-(U1-D1{slash}TX-Pad1)") (class "Default")
      (node (ref "U1") (pin "1") (pinfunction "D1/TX_1") (pintype "unspecified"))
    )
    (net (code "98") (name "unconnected-(U1-D13{slash}SCK-Pad16)") (class "Default")
      (node (ref "U1") (pin "16") (pinfunction "D13/SCK_16") (pintype "unspecified"))
    )
    (net (code "99") (name "unconnected-(U1-GND-Pad4)") (class "Default")
      (node (ref "U1") (pin "4") (pinfunction "GND_4") (pintype "unspecified"))
    )
    (net (code "100") (name "unconnected-(U1-RESET-Pad3)") (class "Default")
      (node (ref "U1") (pin "3") (pinfunction "RESET_3") (pintype "unspecified"))
    )
    (net (code "101") (name "unconnected-(U1-RESET-Pad28)") (class "Default")
      (node (ref "U1") (pin "28") (pinfunction "RESET_28") (pintype "unspecified"))
    )
    (net (code "102") (name "unconnected-(U2-CLK-Pad10)") (class "Default")
      (node (ref "U2") (pin "10") (pinfunction "CLK_10") (pintype "unspecified"))
    )
    (net (code "103") (name "unconnected-(U2-CS-Pad9)") (class "Default")
      (node (ref "U2") (pin "9") (pinfunction "CS_9") (pintype "unspecified"))
    )
    (net (code "104") (name "unconnected-(U2-DIN-Pad8)") (class "Default")
      (node (ref "U2") (pin "8") (pinfunction "DIN_8") (pintype "unspecified"))
    )
    (net (code "105") (name "unconnected-(U2-GND-Pad7)") (class "Default")
      (node (ref "U2") (pin "7") (pinfunction "GND_7") (pintype "unspecified"))
    )
    (net (code "106") (name "unconnected-(U2-VCC-Pad6)") (class "Default")
      (node (ref "U2") (pin "6") (pinfunction "VCC_6") (pintype "unspecified"))
    )
  )
)
